# relay3.net
KiCad netlist of a schematic drawn in EAGLE
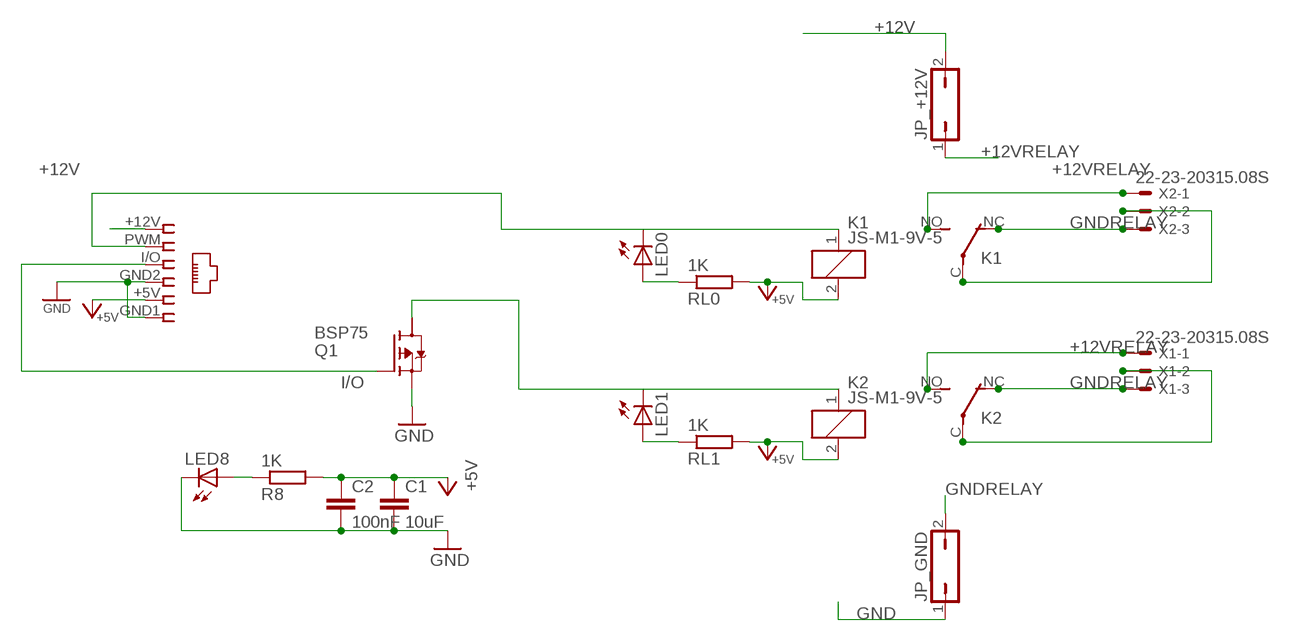
[diagram p0: schematic, sheet 1]

(export (version "E")
  (design (tool "Eeschema 10.0.6"))
  (components
    (comp (ref "C1")
      (value "10uF")
      (footprint "eagle-import:C1206")
      (libsource (lib "eagle-import") (part "C-EUC1206"))
    )
    (comp (ref "C2")
      (value "100nF")
      (footprint "eagle-import:C1206")
      (libsource (lib "eagle-import") (part "C-EUC1206"))
    )
    (comp (ref "I/O_PWM")
      (value "I2C 1")
      (footprint "eagle-import:RJ12-STRAIGHT")
      (libsource (lib "eagle-import") (part "RJ12STRAIGHT"))
    )
    (comp (ref "JP_+12V")
      (value "JP1Q")
      (footprint "eagle-import:JP1")
      (libsource (lib "eagle-import") (part "JP1Q"))
    )
    (comp (ref "JP_GND")
      (value "JP1Q")
      (footprint "eagle-import:JP1")
      (libsource (lib "eagle-import") (part "JP1Q"))
    )
    (comp (ref "K1")
      (value "JS-M1-9V-5")
      (footprint "eagle-import:JS-M")
      (libsource (lib "eagle-import") (part "JS-M1-9V-5"))
    )
    (comp (ref "K2")
      (value "JS-M1-9V-5")
      (footprint "eagle-import:JS-M")
      (libsource (lib "eagle-import") (part "JS-M1-9V-5"))
    )
    (comp (ref "LED0")
      (value "LED1206")
      (footprint "eagle-import:LED-1206")
      (libsource (lib "eagle-import") (part "LED1206"))
    )
    (comp (ref "LED1")
      (value "LED1206")
      (footprint "eagle-import:LED-1206")
      (libsource (lib "eagle-import") (part "LED1206"))
    )
    (comp (ref "LED8")
      (value "LED1206")
      (footprint "eagle-import:LED-1206")
      (libsource (lib "eagle-import") (part "LED1206"))
    )
    (comp (ref "Q1")
      (value "BSP75")
      (footprint "eagle-import:PG-SOT-223")
      (libsource (lib "eagle-import") (part "BSP613P"))
    )
    (comp (ref "R8")
      (value "1K")
      (footprint "eagle-import:M1206")
      (libsource (lib "eagle-import") (part "R-EU_M1206"))
    )
    (comp (ref "RL0")
      (value "1K")
      (footprint "eagle-import:M1206")
      (libsource (lib "eagle-import") (part "R-EU_M1206"))
    )
    (comp (ref "RL1")
      (value "1K")
      (footprint "eagle-import:M1206")
      (libsource (lib "eagle-import") (part "R-EU_M1206"))
    )
    (comp (ref "X1")
      (value "22-23-20315.08S")
      (footprint "eagle-import:3-PIN-5.08S")
      (libsource (lib "eagle-import") (part "22-23-20315.08S"))
    )
    (comp (ref "X2")
      (value "22-23-20315.08S")
      (footprint "eagle-import:3-PIN-5.08S")
      (libsource (lib "eagle-import") (part "22-23-20315.08S"))
    )
  )
  (nets
    (net (code "1") (name "+5V") (class "Default")
      (node (ref "C1") (pin "1") (pinfunction "1_1") (pintype "passive"))
      (node (ref "C2") (pin "1") (pinfunction "1_1") (pintype "passive"))
      (node (ref "I/O_PWM") (pin "+5V") (pinfunction "5_+5V") (pintype "bidirectional"))
      (node (ref "K1") (pin "2") (pinfunction "2_2") (pintype "passive"))
      (node (ref "K2") (pin "2") (pinfunction "2_2") (pintype "passive"))
      (node (ref "R8") (pin "2") (pinfunction "2_2") (pintype "passive"))
      (node (ref "RL0") (pin "2") (pinfunction "2_2") (pintype "passive"))
      (node (ref "RL1") (pin "2") (pinfunction "2_2") (pintype "passive"))
    )
    (net (code "2") (name "/+12V") (class "Default")
      (node (ref "I/O_PWM") (pin "+12V") (pinfunction "1_+12V") (pintype "bidirectional"))
      (node (ref "JP_+12V") (pin "2") (pinfunction "2_2") (pintype "passive"))
    )
    (net (code "3") (name "/+12VRELAY") (class "Default")
      (node (ref "JP_+12V") (pin "1") (pinfunction "1_1") (pintype "passive"))
      (node (ref "K1") (pin "NO") (pinfunction "S_NO") (pintype "passive"))
      (node (ref "K2") (pin "NO") (pinfunction "S_NO") (pintype "passive"))
      (node (ref "X1") (pin "1") (pinfunction "S_1") (pintype "passive"))
      (node (ref "X2") (pin "1") (pinfunction "S_1") (pintype "passive"))
    )
    (net (code "4") (name "/GNDRELAY") (class "Default")
      (node (ref "JP_GND") (pin "2") (pinfunction "2_2") (pintype "passive"))
      (node (ref "K1") (pin "NC") (pinfunction "O_NC") (pintype "passive"))
      (node (ref "K2") (pin "NC") (pinfunction "O_NC") (pintype "passive"))
      (node (ref "X1") (pin "3") (pinfunction "S_3") (pintype "passive"))
      (node (ref "X2") (pin "3") (pinfunction "S_3") (pintype "passive"))
    )
    (net (code "5") (name "/I{slash}O") (class "Default")
      (node (ref "I/O_PWM") (pin "I/O") (pinfunction "3_I/O") (pintype "bidirectional"))
      (node (ref "Q1") (pin "1") (pinfunction "G_1") (pintype "passive"))
    )
    (net (code "6") (name "GND") (class "Default")
      (node (ref "C1") (pin "2") (pinfunction "2_2") (pintype "passive"))
      (node (ref "C2") (pin "2") (pinfunction "2_2") (pintype "passive"))
      (node (ref "I/O_PWM") (pin "GND1") (pinfunction "6_GND1") (pintype "bidirectional"))
      (node (ref "I/O_PWM") (pin "GND2") (pinfunction "4_GND2") (pintype "bidirectional"))
      (node (ref "JP_GND") (pin "1") (pinfunction "1_1") (pintype "passive"))
      (node (ref "LED8") (pin "C") (pinfunction "C_C") (pintype "passive"))
      (node (ref "Q1") (pin "3") (pinfunction "S_3") (pintype "passive"))
    )
    (net (code "7") (name "Net-(I/O_PWM-2)") (class "Default")
      (node (ref "I/O_PWM") (pin "PWM") (pinfunction "2_PWM") (pintype "bidirectional"))
      (node (ref "K1") (pin "1") (pinfunction "1_1") (pintype "passive"))
      (node (ref "LED0") (pin "C") (pinfunction "C_C") (pintype "passive"))
    )
    (net (code "8") (name "Net-(K1B-P)") (class "Default")
      (node (ref "K1") (pin "C") (pinfunction "P_C") (pintype "passive"))
      (node (ref "X2") (pin "2") (pinfunction "S_2") (pintype "passive"))
    )
    (net (code "9") (name "Net-(K2-Pad1)") (class "Default")
      (node (ref "K2") (pin "1") (pinfunction "1_1") (pintype "passive"))
      (node (ref "LED1") (pin "C") (pinfunction "C_C") (pintype "passive"))
      (node (ref "Q1") (pin "2") (pinfunction "D_2") (pintype "passive"))
    )
    (net (code "10") (name "Net-(K2B-P)") (class "Default")
      (node (ref "K2") (pin "C") (pinfunction "P_C") (pintype "passive"))
      (node (ref "X1") (pin "2") (pinfunction "S_2") (pintype "passive"))
    )
    (net (code "11") (name "Net-(LED0-PadA)") (class "Default")
      (node (ref "LED0") (pin "A") (pinfunction "A_A") (pintype "passive"))
      (node (ref "RL0") (pin "1") (pinfunction "1_1") (pintype "passive"))
    )
    (net (code "12") (name "Net-(LED1-PadA)") (class "Default")
      (node (ref "LED1") (pin "A") (pinfunction "A_A") (pintype "passive"))
      (node (ref "RL1") (pin "1") (pinfunction "1_1") (pintype "passive"))
    )
    (net (code "13") (name "Net-(LED8-PadA)") (class "Default")
      (node (ref "LED8") (pin "A") (pinfunction "A_A") (pintype "passive"))
      (node (ref "R8") (pin "1") (pinfunction "1_1") (pintype "passive"))
    )
    (net (code "14") (name "unconnected-(Q1-D-Pad4)") (class "Default")
      (node (ref "Q1") (pin "4") (pinfunction "D_4") (pintype "passive"))
    )
  )
)
